# HOMADOS.net
KiCad netlist of a schematic drawn in EAGLE
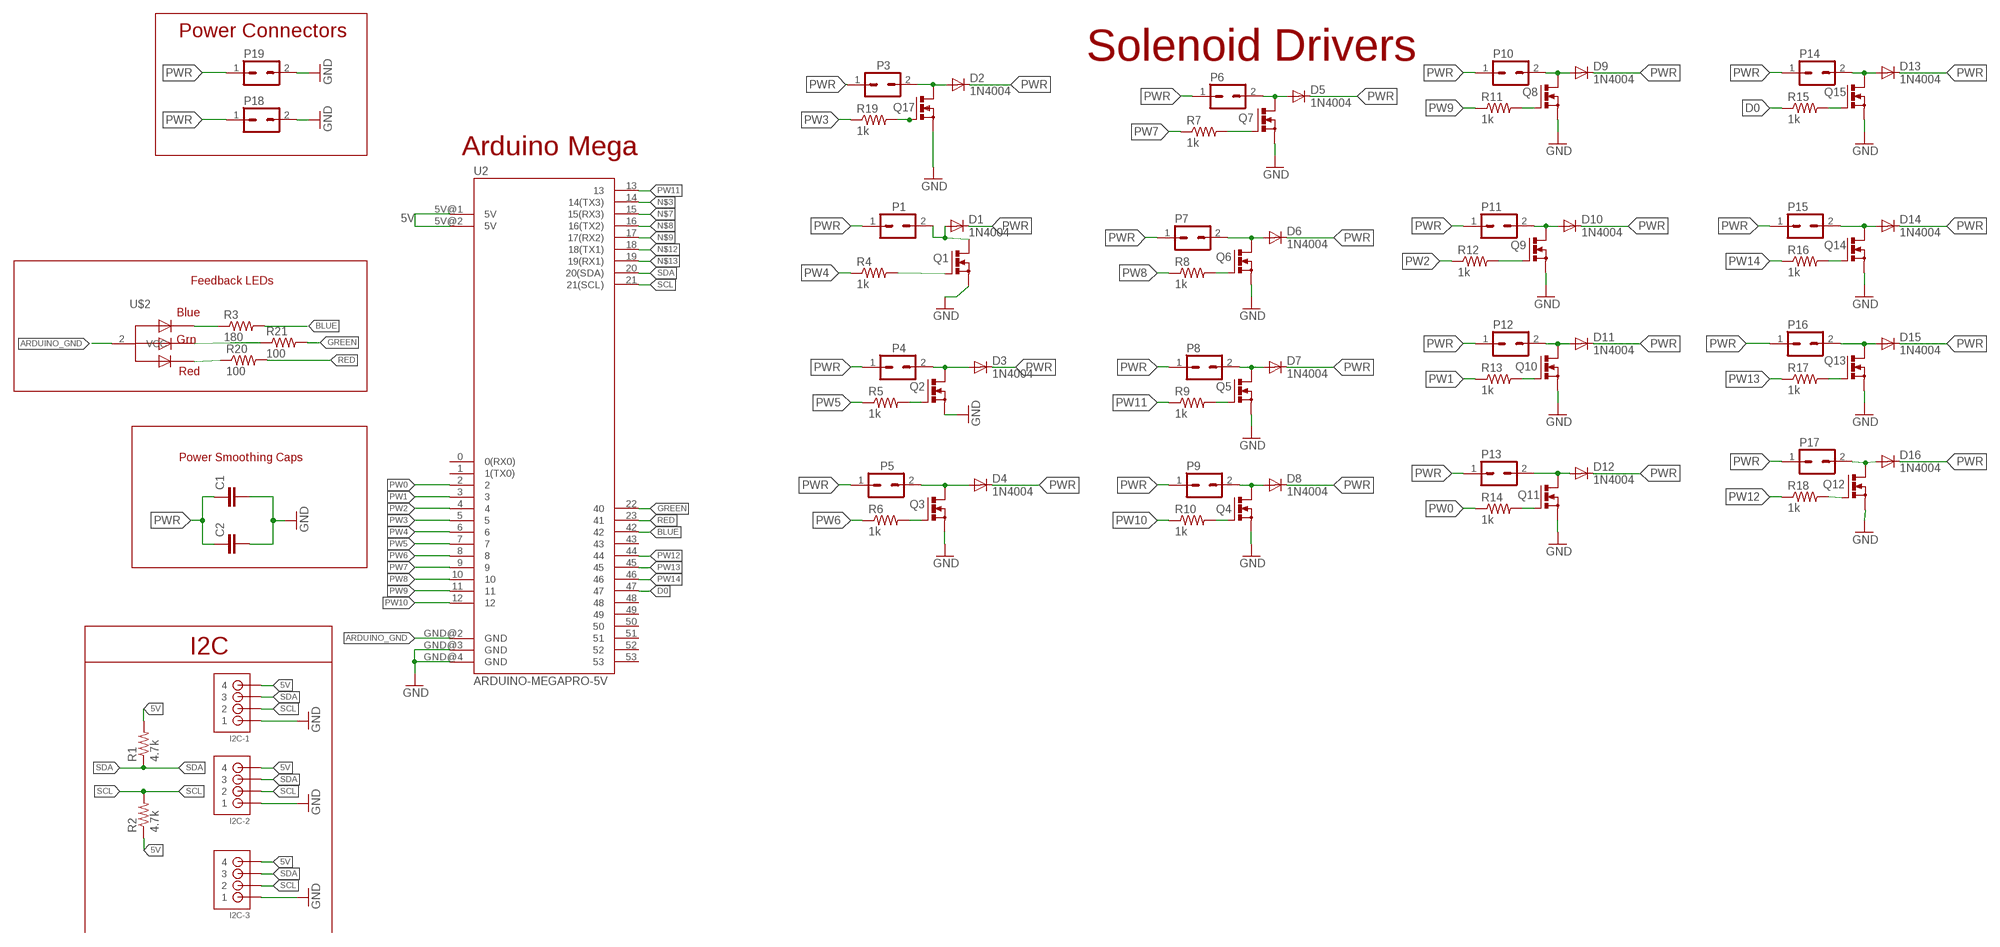
[diagram p0: schematic, sheet 1]

(export (version "E")
  (design (tool "Eeschema 10.0.6"))
  (components
    (comp (ref "C1")
      (value "CAPPTH1")
      (footprint "eagle-import:CAP-PTH-5MM")
      (libsource (lib "eagle-import") (part "CAPPTH1"))
    )
    (comp (ref "C2")
      (value "CAPPTH3")
      (footprint "eagle-import:CAP-PTH-LARGE")
      (libsource (lib "eagle-import") (part "CAPPTH3"))
    )
    (comp (ref "D1")
      (value "1N4004")
      (footprint "eagle-import:DO41-10")
      (libsource (lib "eagle-import") (part "1N4004"))
    )
    (comp (ref "D2")
      (value "1N4004")
      (footprint "eagle-import:DO41-10")
      (libsource (lib "eagle-import") (part "1N4004"))
    )
    (comp (ref "D3")
      (value "1N4004")
      (footprint "eagle-import:DO41-10")
      (libsource (lib "eagle-import") (part "1N4004"))
    )
    (comp (ref "D4")
      (value "1N4004")
      (footprint "eagle-import:DO41-10")
      (libsource (lib "eagle-import") (part "1N4004"))
    )
    (comp (ref "D5")
      (value "1N4004")
      (footprint "eagle-import:DO41-10")
      (libsource (lib "eagle-import") (part "1N4004"))
    )
    (comp (ref "D6")
      (value "1N4004")
      (footprint "eagle-import:DO41-10")
      (libsource (lib "eagle-import") (part "1N4004"))
    )
    (comp (ref "D7")
      (value "1N4004")
      (footprint "eagle-import:DO41-10")
      (libsource (lib "eagle-import") (part "1N4004"))
    )
    (comp (ref "D8")
      (value "1N4004")
      (footprint "eagle-import:DO41-10")
      (libsource (lib "eagle-import") (part "1N4004"))
    )
    (comp (ref "D9")
      (value "1N4004")
      (footprint "eagle-import:DO41-10")
      (libsource (lib "eagle-import") (part "1N4004"))
    )
    (comp (ref "D10")
      (value "1N4004")
      (footprint "eagle-import:DO41-10")
      (libsource (lib "eagle-import") (part "1N4004"))
    )
    (comp (ref "D11")
      (value "1N4004")
      (footprint "eagle-import:DO41-10")
      (libsource (lib "eagle-import") (part "1N4004"))
    )
    (comp (ref "D12")
      (value "1N4004")
      (footprint "eagle-import:DO41-10")
      (libsource (lib "eagle-import") (part "1N4004"))
    )
    (comp (ref "D13")
      (value "1N4004")
      (footprint "eagle-import:DO41-10")
      (libsource (lib "eagle-import") (part "1N4004"))
    )
    (comp (ref "D14")
      (value "1N4004")
      (footprint "eagle-import:DO41-10")
      (libsource (lib "eagle-import") (part "1N4004"))
    )
    (comp (ref "D15")
      (value "1N4004")
      (footprint "eagle-import:DO41-10")
      (libsource (lib "eagle-import") (part "1N4004"))
    )
    (comp (ref "D16")
      (value "1N4004")
      (footprint "eagle-import:DO41-10")
      (libsource (lib "eagle-import") (part "1N4004"))
    )
    (comp (ref "I2C-1")
      (value "JST-PH_4-PIN_HEADER")
      (footprint "eagle-import:JST_B4B-PH_HEADER")
      (libsource (lib "eagle-import") (part "JST-PH_4-PIN_HEADER"))
    )
    (comp (ref "I2C-2")
      (value "JST-PH_4-PIN_HEADER")
      (footprint "eagle-import:JST_B4B-PH_HEADER")
      (libsource (lib "eagle-import") (part "JST-PH_4-PIN_HEADER"))
    )
    (comp (ref "I2C-3")
      (value "JST-PH_4-PIN_HEADER")
      (footprint "eagle-import:JST_B4B-PH_HEADER")
      (libsource (lib "eagle-import") (part "JST-PH_4-PIN_HEADER"))
    )
    (comp (ref "P1")
      (value "39-30-02")
      (footprint "eagle-import:39-30-_02_")
      (libsource (lib "eagle-import") (part "39-30-?02?"))
    )
    (comp (ref "P3")
      (value "39-30-02")
      (footprint "eagle-import:39-30-_02_")
      (libsource (lib "eagle-import") (part "39-30-?02?"))
    )
    (comp (ref "P4")
      (value "39-30-02")
      (footprint "eagle-import:39-30-_02_")
      (libsource (lib "eagle-import") (part "39-30-?02?"))
    )
    (comp (ref "P5")
      (value "39-30-02")
      (footprint "eagle-import:39-30-_02_")
      (libsource (lib "eagle-import") (part "39-30-?02?"))
    )
    (comp (ref "P6")
      (value "39-30-02")
      (footprint "eagle-import:39-30-_02_")
      (libsource (lib "eagle-import") (part "39-30-?02?"))
    )
    (comp (ref "P7")
      (value "39-30-02")
      (footprint "eagle-import:39-30-_02_")
      (libsource (lib "eagle-import") (part "39-30-?02?"))
    )
    (comp (ref "P8")
      (value "39-30-02")
      (footprint "eagle-import:39-30-_02_")
      (libsource (lib "eagle-import") (part "39-30-?02?"))
    )
    (comp (ref "P9")
      (value "39-30-02")
      (footprint "eagle-import:39-30-_02_")
      (libsource (lib "eagle-import") (part "39-30-?02?"))
    )
    (comp (ref "P10")
      (value "39-30-02")
      (footprint "eagle-import:39-30-_02_")
      (libsource (lib "eagle-import") (part "39-30-?02?"))
    )
    (comp (ref "P11")
      (value "39-30-02")
      (footprint "eagle-import:39-30-_02_")
      (libsource (lib "eagle-import") (part "39-30-?02?"))
    )
    (comp (ref "P12")
      (value "39-30-02")
      (footprint "eagle-import:39-30-_02_")
      (libsource (lib "eagle-import") (part "39-30-?02?"))
    )
    (comp (ref "P13")
      (value "39-30-02")
      (footprint "eagle-import:39-30-_02_")
      (libsource (lib "eagle-import") (part "39-30-?02?"))
    )
    (comp (ref "P14")
      (value "39-30-02")
      (footprint "eagle-import:39-30-_02_")
      (libsource (lib "eagle-import") (part "39-30-?02?"))
    )
    (comp (ref "P15")
      (value "39-30-02")
      (footprint "eagle-import:39-30-_02_")
      (libsource (lib "eagle-import") (part "39-30-?02?"))
    )
    (comp (ref "P16")
      (value "39-30-02")
      (footprint "eagle-import:39-30-_02_")
      (libsource (lib "eagle-import") (part "39-30-?02?"))
    )
    (comp (ref "P17")
      (value "39-30-02")
      (footprint "eagle-import:39-30-_02_")
      (libsource (lib "eagle-import") (part "39-30-?02?"))
    )
    (comp (ref "P18")
      (value "39-30-02")
      (footprint "eagle-import:39-30-_02_")
      (libsource (lib "eagle-import") (part "39-30-?02?"))
    )
    (comp (ref "P19")
      (value "39-30-02")
      (footprint "eagle-import:39-30-_02_")
      (libsource (lib "eagle-import") (part "39-30-?02?"))
    )
    (comp (ref "Q1")
      (value "PMOSFET_NTO220BV")
      (footprint "eagle-import:TO220BV")
      (libsource (lib "eagle-import") (part "PMOSFET_NTO220BV"))
    )
    (comp (ref "Q2")
      (value "PMOSFET_NTO220BV")
      (footprint "eagle-import:TO220BV")
      (libsource (lib "eagle-import") (part "PMOSFET_NTO220BV"))
    )
    (comp (ref "Q3")
      (value "PMOSFET_NTO220BV")
      (footprint "eagle-import:TO220BV")
      (libsource (lib "eagle-import") (part "PMOSFET_NTO220BV"))
    )
    (comp (ref "Q4")
      (value "PMOSFET_NTO220BV")
      (footprint "eagle-import:TO220BV")
      (libsource (lib "eagle-import") (part "PMOSFET_NTO220BV"))
    )
    (comp (ref "Q5")
      (value "PMOSFET_NTO220BV")
      (footprint "eagle-import:TO220BV")
      (libsource (lib "eagle-import") (part "PMOSFET_NTO220BV"))
    )
    (comp (ref "Q6")
      (value "PMOSFET_NTO220BV")
      (footprint "eagle-import:TO220BV")
      (libsource (lib "eagle-import") (part "PMOSFET_NTO220BV"))
    )
    (comp (ref "Q7")
      (value "PMOSFET_NTO220BV")
      (footprint "eagle-import:TO220BV")
      (libsource (lib "eagle-import") (part "PMOSFET_NTO220BV"))
    )
    (comp (ref "Q8")
      (value "PMOSFET_NTO220BV")
      (footprint "eagle-import:TO220BV")
      (libsource (lib "eagle-import") (part "PMOSFET_NTO220BV"))
    )
    (comp (ref "Q9")
      (value "PMOSFET_NTO220BV")
      (footprint "eagle-import:TO220BV")
      (libsource (lib "eagle-import") (part "PMOSFET_NTO220BV"))
    )
    (comp (ref "Q10")
      (value "PMOSFET_NTO220BV")
      (footprint "eagle-import:TO220BV")
      (libsource (lib "eagle-import") (part "PMOSFET_NTO220BV"))
    )
    (comp (ref "Q11")
      (value "PMOSFET_NTO220BV")
      (footprint "eagle-import:TO220BV")
      (libsource (lib "eagle-import") (part "PMOSFET_NTO220BV"))
    )
    (comp (ref "Q12")
      (value "PMOSFET_NTO220BV")
      (footprint "eagle-import:TO220BV")
      (libsource (lib "eagle-import") (part "PMOSFET_NTO220BV"))
    )
    (comp (ref "Q13")
      (value "PMOSFET_NTO220BV")
      (footprint "eagle-import:TO220BV")
      (libsource (lib "eagle-import") (part "PMOSFET_NTO220BV"))
    )
    (comp (ref "Q14")
      (value "PMOSFET_NTO220BV")
      (footprint "eagle-import:TO220BV")
      (libsource (lib "eagle-import") (part "PMOSFET_NTO220BV"))
    )
    (comp (ref "Q15")
      (value "PMOSFET_NTO220BV")
      (footprint "eagle-import:TO220BV")
      (libsource (lib "eagle-import") (part "PMOSFET_NTO220BV"))
    )
    (comp (ref "Q17")
      (value "PMOSFET_NTO220BV")
      (footprint "eagle-import:TO220BV")
      (libsource (lib "eagle-import") (part "PMOSFET_NTO220BV"))
    )
    (comp (ref "R1")
      (value "4.7k")
      (footprint "eagle-import:AXIAL-0.3-KIT")
      (libsource (lib "eagle-import") (part "RESISTORKIT"))
    )
    (comp (ref "R2")
      (value "4.7k")
      (footprint "eagle-import:AXIAL-0.3-KIT")
      (libsource (lib "eagle-import") (part "RESISTORKIT"))
    )
    (comp (ref "R3")
      (value "180")
      (footprint "eagle-import:AXIAL-0.3-KIT")
      (libsource (lib "eagle-import") (part "RESISTORKIT"))
    )
    (comp (ref "R4")
      (value "1k")
      (footprint "eagle-import:AXIAL-0.3-KIT")
      (libsource (lib "eagle-import") (part "RESISTORKIT"))
    )
    (comp (ref "R5")
      (value "1k")
      (footprint "eagle-import:AXIAL-0.3-KIT")
      (libsource (lib "eagle-import") (part "RESISTORKIT"))
    )
    (comp (ref "R6")
      (value "1k")
      (footprint "eagle-import:AXIAL-0.3-KIT")
      (libsource (lib "eagle-import") (part "RESISTORKIT"))
    )
    (comp (ref "R7")
      (value "1k")
      (footprint "eagle-import:AXIAL-0.3-KIT")
      (libsource (lib "eagle-import") (part "RESISTORKIT"))
    )
    (comp (ref "R8")
      (value "1k")
      (footprint "eagle-import:AXIAL-0.3-KIT")
      (libsource (lib "eagle-import") (part "RESISTORKIT"))
    )
    (comp (ref "R9")
      (value "1k")
      (footprint "eagle-import:AXIAL-0.3-KIT")
      (libsource (lib "eagle-import") (part "RESISTORKIT"))
    )
    (comp (ref "R10")
      (value "1k")
      (footprint "eagle-import:AXIAL-0.3-KIT")
      (libsource (lib "eagle-import") (part "RESISTORKIT"))
    )
    (comp (ref "R11")
      (value "1k")
      (footprint "eagle-import:AXIAL-0.3-KIT")
      (libsource (lib "eagle-import") (part "RESISTORKIT"))
    )
    (comp (ref "R12")
      (value "1k")
      (footprint "eagle-import:AXIAL-0.3-KIT")
      (libsource (lib "eagle-import") (part "RESISTORKIT"))
    )
    (comp (ref "R13")
      (value "1k")
      (footprint "eagle-import:AXIAL-0.3-KIT")
      (libsource (lib "eagle-import") (part "RESISTORKIT"))
    )
    (comp (ref "R14")
      (value "1k")
      (footprint "eagle-import:AXIAL-0.3-KIT")
      (libsource (lib "eagle-import") (part "RESISTORKIT"))
    )
    (comp (ref "R15")
      (value "1k")
      (footprint "eagle-import:AXIAL-0.3-KIT")
      (libsource (lib "eagle-import") (part "RESISTORKIT"))
    )
    (comp (ref "R16")
      (value "1k")
      (footprint "eagle-import:AXIAL-0.3-KIT")
      (libsource (lib "eagle-import") (part "RESISTORKIT"))
    )
    (comp (ref "R17")
      (value "1k")
      (footprint "eagle-import:AXIAL-0.3-KIT")
      (libsource (lib "eagle-import") (part "RESISTORKIT"))
    )
    (comp (ref "R18")
      (value "1k")
      (footprint "eagle-import:AXIAL-0.3-KIT")
      (libsource (lib "eagle-import") (part "RESISTORKIT"))
    )
    (comp (ref "R19")
      (value "1k")
      (footprint "eagle-import:AXIAL-0.3-KIT")
      (libsource (lib "eagle-import") (part "RESISTORKIT"))
    )
    (comp (ref "R20")
      (value "100")
      (footprint "eagle-import:AXIAL-0.3-KIT")
      (libsource (lib "eagle-import") (part "RESISTORKIT"))
    )
    (comp (ref "R21")
      (value "100")
      (footprint "eagle-import:AXIAL-0.3-KIT")
      (libsource (lib "eagle-import") (part "RESISTORKIT"))
    )
    (comp (ref "U$2")
      (value "RGBLED_CA")
      (footprint "eagle-import:LED5MMRGB")
      (libsource (lib "eagle-import") (part "RGBLED_CA"))
    )
    (comp (ref "U2")
      (value "ARDUINO-MEGAPRO-5V")
      (footprint "eagle-import:ARDUINO_MEGA-PRO-5V")
      (libsource (lib "eagle-import") (part "ARDUINO-MEGAPRO-5V"))
    )
  )
  (nets
    (net (code "1") (name "5V") (class "Default")
      (node (ref "I2C-1") (pin "P4") (pinfunction "4_P4") (pintype "bidirectional"))
      (node (ref "I2C-2") (pin "P4") (pinfunction "4_P4") (pintype "bidirectional"))
      (node (ref "I2C-3") (pin "P4") (pinfunction "4_P4") (pintype "bidirectional"))
      (node (ref "R1") (pin "P$2") (pinfunction "2_P$2") (pintype "passive"))
      (node (ref "R2") (pin "P$1") (pinfunction "1_P$1") (pintype "passive"))
      (node (ref "U2") (pin "5V@1") (pinfunction "5V_5V@1") (pintype "bidirectional"))
      (node (ref "U2") (pin "5V@2") (pinfunction "5V_5V@2") (pintype "bidirectional"))
    )
    (net (code "2") (name "ARDUINO_GND") (class "Default")
      (node (ref "U$2") (pin "2") (pinfunction "VCC_2") (pintype "bidirectional"))
      (node (ref "U2") (pin "GND@2") (pinfunction "GND_GND@2") (pintype "bidirectional"))
    )
    (net (code "3") (name "BLUE") (class "Default")
      (node (ref "R3") (pin "P$2") (pinfunction "2_P$2") (pintype "passive"))
      (node (ref "U2") (pin "42") (pinfunction "42_42") (pintype "bidirectional"))
    )
    (net (code "4") (name "D0") (class "Default")
      (node (ref "R15") (pin "P$1") (pinfunction "1_P$1") (pintype "passive"))
      (node (ref "U2") (pin "47") (pinfunction "47_47") (pintype "bidirectional"))
    )
    (net (code "5") (name "GND") (class "Default")
      (node (ref "C1") (pin "2") (pinfunction "2_2") (pintype "passive"))
      (node (ref "C2") (pin "2") (pinfunction "2_2") (pintype "passive"))
      (node (ref "I2C-1") (pin "P1") (pinfunction "1_P1") (pintype "bidirectional"))
      (node (ref "I2C-2") (pin "P1") (pinfunction "1_P1") (pintype "bidirectional"))
      (node (ref "I2C-3") (pin "P1") (pinfunction "1_P1") (pintype "bidirectional"))
      (node (ref "P18") (pin "2") (pinfunction "2_2") (pintype "passive"))
      (node (ref "P19") (pin "2") (pinfunction "2_2") (pintype "passive"))
      (node (ref "Q1") (pin "S") (pinfunction "S_S") (pintype "passive"))
      (node (ref "Q10") (pin "S") (pinfunction "S_S") (pintype "passive"))
      (node (ref "Q11") (pin "S") (pinfunction "S_S") (pintype "passive"))
      (node (ref "Q12") (pin "S") (pinfunction "S_S") (pintype "passive"))
      (node (ref "Q13") (pin "S") (pinfunction "S_S") (pintype "passive"))
      (node (ref "Q14") (pin "S") (pinfunction "S_S") (pintype "passive"))
      (node (ref "Q15") (pin "S") (pinfunction "S_S") (pintype "passive"))
      (node (ref "Q17") (pin "S") (pinfunction "S_S") (pintype "passive"))
      (node (ref "Q2") (pin "S") (pinfunction "S_S") (pintype "passive"))
      (node (ref "Q3") (pin "S") (pinfunction "S_S") (pintype "passive"))
      (node (ref "Q4") (pin "S") (pinfunction "S_S") (pintype "passive"))
      (node (ref "Q5") (pin "S") (pinfunction "S_S") (pintype "passive"))
      (node (ref "Q6") (pin "S") (pinfunction "S_S") (pintype "passive"))
      (node (ref "Q7") (pin "S") (pinfunction "S_S") (pintype "passive"))
      (node (ref "Q8") (pin "S") (pinfunction "S_S") (pintype "passive"))
      (node (ref "Q9") (pin "S") (pinfunction "S_S") (pintype "passive"))
      (node (ref "U2") (pin "GND@3") (pinfunction "GND_GND@3") (pintype "bidirectional"))
      (node (ref "U2") (pin "GND@4") (pinfunction "GND_GND@4") (pintype "bidirectional"))
    )
    (net (code "6") (name "GREEN") (class "Default")
      (node (ref "R21") (pin "P$2") (pinfunction "2_P$2") (pintype "passive"))
      (node (ref "U2") (pin "22") (pinfunction "40_22") (pintype "bidirectional"))
    )
    (net (code "7") (name "N$3") (class "Default")
      (node (ref "U2") (pin "14") (pinfunction "14(TX3)_14") (pintype "bidirectional"))
    )
    (net (code "8") (name "N$7") (class "Default")
      (node (ref "U2") (pin "15") (pinfunction "15(RX3)_15") (pintype "bidirectional"))
    )
    (net (code "9") (name "N$8") (class "Default")
      (node (ref "U2") (pin "16") (pinfunction "16(TX2)_16") (pintype "bidirectional"))
    )
    (net (code "10") (name "N$9") (class "Default")
      (node (ref "U2") (pin "17") (pinfunction "17(RX2)_17") (pintype "bidirectional"))
    )
    (net (code "11") (name "N$12") (class "Default")
      (node (ref "U2") (pin "18") (pinfunction "18(TX1)_18") (pintype "bidirectional"))
    )
    (net (code "12") (name "N$13") (class "Default")
      (node (ref "U2") (pin "19") (pinfunction "19(RX1)_19") (pintype "bidirectional"))
    )
    (net (code "13") (name "Net-(D1-PadA)") (class "Default")
      (node (ref "D1") (pin "A") (pinfunction "A_A") (pintype "passive"))
      (node (ref "P1") (pin "2") (pinfunction "2_2") (pintype "passive"))
      (node (ref "Q1") (pin "D") (pinfunction "D_D") (pintype "passive"))
    )
    (net (code "14") (name "Net-(D2-PadA)") (class "Default")
      (node (ref "D2") (pin "A") (pinfunction "A_A") (pintype "passive"))
      (node (ref "P3") (pin "2") (pinfunction "2_2") (pintype "passive"))
      (node (ref "Q17") (pin "D") (pinfunction "D_D") (pintype "passive"))
    )
    (net (code "15") (name "Net-(D3-PadA)") (class "Default")
      (node (ref "D3") (pin "A") (pinfunction "A_A") (pintype "passive"))
      (node (ref "P4") (pin "2") (pinfunction "2_2") (pintype "passive"))
      (node (ref "Q2") (pin "D") (pinfunction "D_D") (pintype "passive"))
    )
    (net (code "16") (name "Net-(D4-PadA)") (class "Default")
      (node (ref "D4") (pin "A") (pinfunction "A_A") (pintype "passive"))
      (node (ref "P5") (pin "2") (pinfunction "2_2") (pintype "passive"))
      (node (ref "Q3") (pin "D") (pinfunction "D_D") (pintype "passive"))
    )
    (net (code "17") (name "Net-(D5-PadA)") (class "Default")
      (node (ref "D5") (pin "A") (pinfunction "A_A") (pintype "passive"))
      (node (ref "P6") (pin "2") (pinfunction "2_2") (pintype "passive"))
      (node (ref "Q7") (pin "D") (pinfunction "D_D") (pintype "passive"))
    )
    (net (code "18") (name "Net-(D6-PadA)") (class "Default")
      (node (ref "D6") (pin "A") (pinfunction "A_A") (pintype "passive"))
      (node (ref "P7") (pin "2") (pinfunction "2_2") (pintype "passive"))
      (node (ref "Q6") (pin "D") (pinfunction "D_D") (pintype "passive"))
    )
    (net (code "19") (name "Net-(D7-PadA)") (class "Default")
      (node (ref "D7") (pin "A") (pinfunction "A_A") (pintype "passive"))
      (node (ref "P8") (pin "2") (pinfunction "2_2") (pintype "passive"))
      (node (ref "Q5") (pin "D") (pinfunction "D_D") (pintype "passive"))
    )
    (net (code "20") (name "Net-(D8-PadA)") (class "Default")
      (node (ref "D8") (pin "A") (pinfunction "A_A") (pintype "passive"))
      (node (ref "P9") (pin "2") (pinfunction "2_2") (pintype "passive"))
      (node (ref "Q4") (pin "D") (pinfunction "D_D") (pintype "passive"))
    )
    (net (code "21") (name "Net-(D9-PadA)") (class "Default")
      (node (ref "D9") (pin "A") (pinfunction "A_A") (pintype "passive"))
      (node (ref "P10") (pin "2") (pinfunction "2_2") (pintype "passive"))
      (node (ref "Q8") (pin "D") (pinfunction "D_D") (pintype "passive"))
    )
    (net (code "22") (name "Net-(D10-PadA)") (class "Default")
      (node (ref "D10") (pin "A") (pinfunction "A_A") (pintype "passive"))
      (node (ref "P11") (pin "2") (pinfunction "2_2") (pintype "passive"))
      (node (ref "Q9") (pin "D") (pinfunction "D_D") (pintype "passive"))
    )
    (net (code "23") (name "Net-(D11-PadA)") (class "Default")
      (node (ref "D11") (pin "A") (pinfunction "A_A") (pintype "passive"))
      (node (ref "P12") (pin "2") (pinfunction "2_2") (pintype "passive"))
      (node (ref "Q10") (pin "D") (pinfunction "D_D") (pintype "passive"))
    )
    (net (code "24") (name "Net-(D12-PadA)") (class "Default")
      (node (ref "D12") (pin "A") (pinfunction "A_A") (pintype "passive"))
      (node (ref "P13") (pin "2") (pinfunction "2_2") (pintype "passive"))
      (node (ref "Q11") (pin "D") (pinfunction "D_D") (pintype "passive"))
    )
    (net (code "25") (name "Net-(D13-PadA)") (class "Default")
      (node (ref "D13") (pin "A") (pinfunction "A_A") (pintype "passive"))
      (node (ref "P14") (pin "2") (pinfunction "2_2") (pintype "passive"))
      (node (ref "Q15") (pin "D") (pinfunction "D_D") (pintype "passive"))
    )
    (net (code "26") (name "Net-(D14-PadA)") (class "Default")
      (node (ref "D14") (pin "A") (pinfunction "A_A") (pintype "passive"))
      (node (ref "P15") (pin "2") (pinfunction "2_2") (pintype "passive"))
      (node (ref "Q14") (pin "D") (pinfunction "D_D") (pintype "passive"))
    )
    (net (code "27") (name "Net-(D15-PadA)") (class "Default")
      (node (ref "D15") (pin "A") (pinfunction "A_A") (pintype "passive"))
      (node (ref "P16") (pin "2") (pinfunction "2_2") (pintype "passive"))
      (node (ref "Q13") (pin "D") (pinfunction "D_D") (pintype "passive"))
    )
    (net (code "28") (name "Net-(D16-PadA)") (class "Default")
      (node (ref "D16") (pin "A") (pinfunction "A_A") (pintype "passive"))
      (node (ref "P17") (pin "2") (pinfunction "2_2") (pintype "passive"))
      (node (ref "Q12") (pin "D") (pinfunction "D_D") (pintype "passive"))
    )
    (net (code "29") (name "Net-(R3-1)") (class "Default")
      (node (ref "R3") (pin "P$1") (pinfunction "1_P$1") (pintype "passive"))
      (node (ref "U$2") (pin "4") (pinfunction "BLUE_4") (pintype "bidirectional"))
    )
    (net (code "30") (name "Net-(R4-2)") (class "Default")
      (node (ref "Q1") (pin "G") (pinfunction "G_G") (pintype "passive"))
      (node (ref "R4") (pin "P$2") (pinfunction "2_P$2") (pintype "passive"))
    )
    (net (code "31") (name "Net-(R5-2)") (class "Default")
      (node (ref "Q2") (pin "G") (pinfunction "G_G") (pintype "passive"))
      (node (ref "R5") (pin "P$2") (pinfunction "2_P$2") (pintype "passive"))
    )
    (net (code "32") (name "Net-(R6-2)") (class "Default")
      (node (ref "Q3") (pin "G") (pinfunction "G_G") (pintype "passive"))
      (node (ref "R6") (pin "P$2") (pinfunction "2_P$2") (pintype "passive"))
    )
    (net (code "33") (name "Net-(R7-2)") (class "Default")
      (node (ref "Q7") (pin "G") (pinfunction "G_G") (pintype "passive"))
      (node (ref "R7") (pin "P$2") (pinfunction "2_P$2") (pintype "passive"))
    )
    (net (code "34") (name "Net-(R8-2)") (class "Default")
      (node (ref "Q6") (pin "G") (pinfunction "G_G") (pintype "passive"))
      (node (ref "R8") (pin "P$2") (pinfunction "2_P$2") (pintype "passive"))
    )
    (net (code "35") (name "Net-(R9-2)") (class "Default")
      (node (ref "Q5") (pin "G") (pinfunction "G_G") (pintype "passive"))
      (node (ref "R9") (pin "P$2") (pinfunction "2_P$2") (pintype "passive"))
    )
    (net (code "36") (name "Net-(R10-2)") (class "Default")
      (node (ref "Q4") (pin "G") (pinfunction "G_G") (pintype "passive"))
      (node (ref "R10") (pin "P$2") (pinfunction "2_P$2") (pintype "passive"))
    )
    (net (code "37") (name "Net-(R11-2)") (class "Default")
      (node (ref "Q8") (pin "G") (pinfunction "G_G") (pintype "passive"))
      (node (ref "R11") (pin "P$2") (pinfunction "2_P$2") (pintype "passive"))
    )
    (net (code "38") (name "Net-(R12-2)") (class "Default")
      (node (ref "Q9") (pin "G") (pinfunction "G_G") (pintype "passive"))
      (node (ref "R12") (pin "P$2") (pinfunction "2_P$2") (pintype "passive"))
    )
    (net (code "39") (name "Net-(R13-2)") (class "Default")
      (node (ref "Q10") (pin "G") (pinfunction "G_G") (pintype "passive"))
      (node (ref "R13") (pin "P$2") (pinfunction "2_P$2") (pintype "passive"))
    )
    (net (code "40") (name "Net-(R14-2)") (class "Default")
      (node (ref "Q11") (pin "G") (pinfunction "G_G") (pintype "passive"))
      (node (ref "R14") (pin "P$2") (pinfunction "2_P$2") (pintype "passive"))
    )
    (net (code "41") (name "Net-(R15-2)") (class "Default")
      (node (ref "Q15") (pin "G") (pinfunction "G_G") (pintype "passive"))
      (node (ref "R15") (pin "P$2") (pinfunction "2_P$2") (pintype "passive"))
    )
    (net (code "42") (name "Net-(R16-2)") (class "Default")
      (node (ref "Q14") (pin "G") (pinfunction "G_G") (pintype "passive"))
      (node (ref "R16") (pin "P$2") (pinfunction "2_P$2") (pintype "passive"))
    )
    (net (code "43") (name "Net-(R17-2)") (class "Default")
      (node (ref "Q13") (pin "G") (pinfunction "G_G") (pintype "passive"))
      (node (ref "R17") (pin "P$2") (pinfunction "2_P$2") (pintype "passive"))
    )
    (net (code "44") (name "Net-(R18-2)") (class "Default")
      (node (ref "Q12") (pin "G") (pinfunction "G_G") (pintype "passive"))
      (node (ref "R18") (pin "P$2") (pinfunction "2_P$2") (pintype "passive"))
    )
    (net (code "45") (name "Net-(R19-2)") (class "Default")
      (node (ref "Q17") (pin "G") (pinfunction "G_G") (pintype "passive"))
      (node (ref "R19") (pin "P$2") (pinfunction "2_P$2") (pintype "passive"))
    )
    (net (code "46") (name "Net-(R20-1)") (class "Default")
      (node (ref "R20") (pin "P$1") (pinfunction "1_P$1") (pintype "passive"))
      (node (ref "U$2") (pin "1") (pinfunction "RED_1") (pintype "bidirectional"))
    )
    (net (code "47") (name "Net-(R21-1)") (class "Default")
      (node (ref "R21") (pin "P$1") (pinfunction "1_P$1") (pintype "passive"))
      (node (ref "U$2") (pin "3") (pinfunction "GREEN_3") (pintype "bidirectional"))
    )
    (net (code "48") (name "PW0") (class "Default")
      (node (ref "R14") (pin "P$1") (pinfunction "1_P$1") (pintype "passive"))
      (node (ref "U2") (pin "2") (pinfunction "2_2") (pintype "bidirectional"))
    )
    (net (code "49") (name "PW1") (class "Default")
      (node (ref "R13") (pin "P$1") (pinfunction "1_P$1") (pintype "passive"))
      (node (ref "U2") (pin "3") (pinfunction "3_3") (pintype "bidirectional"))
    )
    (net (code "50") (name "PW2") (class "Default")
      (node (ref "R12") (pin "P$1") (pinfunction "1_P$1") (pintype "passive"))
      (node (ref "U2") (pin "4") (pinfunction "4_4") (pintype "bidirectional"))
    )
    (net (code "51") (name "PW3") (class "Default")
      (node (ref "R19") (pin "P$1") (pinfunction "1_P$1") (pintype "passive"))
      (node (ref "U2") (pin "5") (pinfunction "5_5") (pintype "bidirectional"))
    )
    (net (code "52") (name "PW4") (class "Default")
      (node (ref "R4") (pin "P$1") (pinfunction "1_P$1") (pintype "passive"))
      (node (ref "U2") (pin "6") (pinfunction "6_6") (pintype "bidirectional"))
    )
    (net (code "53") (name "PW5") (class "Default")
      (node (ref "R5") (pin "P$1") (pinfunction "1_P$1") (pintype "passive"))
      (node (ref "U2") (pin "7") (pinfunction "7_7") (pintype "bidirectional"))
    )
    (net (code "54") (name "PW6") (class "Default")
      (node (ref "R6") (pin "P$1") (pinfunction "1_P$1") (pintype "passive"))
      (node (ref "U2") (pin "8") (pinfunction "8_8") (pintype "bidirectional"))
    )
    (net (code "55") (name "PW7") (class "Default")
      (node (ref "R7") (pin "P$1") (pinfunction "1_P$1") (pintype "passive"))
      (node (ref "U2") (pin "9") (pinfunction "9_9") (pintype "bidirectional"))
    )
    (net (code "56") (name "PW8") (class "Default")
      (node (ref "R8") (pin "P$1") (pinfunction "1_P$1") (pintype "passive"))
      (node (ref "U2") (pin "10") (pinfunction "10_10") (pintype "bidirectional"))
    )
    (net (code "57") (name "PW9") (class "Default")
      (node (ref "R11") (pin "P$1") (pinfunction "1_P$1") (pintype "passive"))
      (node (ref "U2") (pin "11") (pinfunction "11_11") (pintype "bidirectional"))
    )
    (net (code "58") (name "PW10") (class "Default")
      (node (ref "R10") (pin "P$1") (pinfunction "1_P$1") (pintype "passive"))
      (node (ref "U2") (pin "12") (pinfunction "12_12") (pintype "bidirectional"))
    )
    (net (code "59") (name "PW11") (class "Default")
      (node (ref "R9") (pin "P$1") (pinfunction "1_P$1") (pintype "passive"))
      (node (ref "U2") (pin "13") (pinfunction "13_13") (pintype "bidirectional"))
    )
    (net (code "60") (name "PW12") (class "Default")
      (node (ref "R18") (pin "P$1") (pinfunction "1_P$1") (pintype "passive"))
      (node (ref "U2") (pin "44") (pinfunction "44_44") (pintype "bidirectional"))
    )
    (net (code "61") (name "PW13") (class "Default")
      (node (ref "R17") (pin "P$1") (pinfunction "1_P$1") (pintype "passive"))
      (node (ref "U2") (pin "45") (pinfunction "45_45") (pintype "bidirectional"))
    )
    (net (code "62") (name "PW14") (class "Default")
      (node (ref "R16") (pin "P$1") (pinfunction "1_P$1") (pintype "passive"))
      (node (ref "U2") (pin "46") (pinfunction "46_46") (pintype "bidirectional"))
    )
    (net (code "63") (name "PWR") (class "Default")
      (node (ref "C1") (pin "1") (pinfunction "1_1") (pintype "passive"))
      (node (ref "C2") (pin "1") (pinfunction "1_1") (pintype "passive"))
      (node (ref "D1") (pin "C") (pinfunction "C_C") (pintype "passive"))
      (node (ref "D10") (pin "C") (pinfunction "C_C") (pintype "passive"))
      (node (ref "D11") (pin "C") (pinfunction "C_C") (pintype "passive"))
      (node (ref "D12") (pin "C") (pinfunction "C_C") (pintype "passive"))
      (node (ref "D13") (pin "C") (pinfunction "C_C") (pintype "passive"))
      (node (ref "D14") (pin "C") (pinfunction "C_C") (pintype "passive"))
      (node (ref "D15") (pin "C") (pinfunction "C_C") (pintype "passive"))
      (node (ref "D16") (pin "C") (pinfunction "C_C") (pintype "passive"))
      (node (ref "D2") (pin "C") (pinfunction "C_C") (pintype "passive"))
      (node (ref "D3") (pin "C") (pinfunction "C_C") (pintype "passive"))
      (node (ref "D4") (pin "C") (pinfunction "C_C") (pintype "passive"))
      (node (ref "D5") (pin "C") (pinfunction "C_C") (pintype "passive"))
      (node (ref "D6") (pin "C") (pinfunction "C_C") (pintype "passive"))
      (node (ref "D7") (pin "C") (pinfunction "C_C") (pintype "passive"))
      (node (ref "D8") (pin "C") (pinfunction "C_C") (pintype "passive"))
      (node (ref "D9") (pin "C") (pinfunction "C_C") (pintype "passive"))
      (node (ref "P1") (pin "1") (pinfunction "1_1") (pintype "passive"))
      (node (ref "P10") (pin "1") (pinfunction "1_1") (pintype "passive"))
      (node (ref "P11") (pin "1") (pinfunction "1_1") (pintype "passive"))
      (node (ref "P12") (pin "1") (pinfunction "1_1") (pintype "passive"))
      (node (ref "P13") (pin "1") (pinfunction "1_1") (pintype "passive"))
      (node (ref "P14") (pin "1") (pinfunction "1_1") (pintype "passive"))
      (node (ref "P15") (pin "1") (pinfunction "1_1") (pintype "passive"))
      (node (ref "P16") (pin "1") (pinfunction "1_1") (pintype "passive"))
      (node (ref "P17") (pin "1") (pinfunction "1_1") (pintype "passive"))
      (node (ref "P18") (pin "1") (pinfunction "1_1") (pintype "passive"))
      (node (ref "P19") (pin "1") (pinfunction "1_1") (pintype "passive"))
      (node (ref "P3") (pin "1") (pinfunction "1_1") (pintype "passive"))
      (node (ref "P4") (pin "1") (pinfunction "1_1") (pintype "passive"))
      (node (ref "P5") (pin "1") (pinfunction "1_1") (pintype "passive"))
      (node (ref "P6") (pin "1") (pinfunction "1_1") (pintype "passive"))
      (node (ref "P7") (pin "1") (pinfunction "1_1") (pintype "passive"))
      (node (ref "P8") (pin "1") (pinfunction "1_1") (pintype "passive"))
      (node (ref "P9") (pin "1") (pinfunction "1_1") (pintype "passive"))
    )
    (net (code "64") (name "RED") (class "Default")
      (node (ref "R20") (pin "P$2") (pinfunction "2_P$2") (pintype "passive"))
      (node (ref "U2") (pin "23") (pinfunction "41_23") (pintype "bidirectional"))
    )
    (net (code "65") (name "SCL") (class "Default")
      (node (ref "I2C-1") (pin "P2") (pinfunction "2_P2") (pintype "bidirectional"))
      (node (ref "I2C-2") (pin "P2") (pinfunction "2_P2") (pintype "bidirectional"))
      (node (ref "I2C-3") (pin "P2") (pinfunction "2_P2") (pintype "bidirectional"))
      (node (ref "R2") (pin "P$2") (pinfunction "2_P$2") (pintype "passive"))
      (node (ref "U2") (pin "21") (pinfunction "21(SCL)_21") (pintype "bidirectional"))
    )
    (net (code "66") (name "SDA") (class "Default")
      (node (ref "I2C-1") (pin "P3") (pinfunction "3_P3") (pintype "bidirectional"))
      (node (ref "I2C-2") (pin "P3") (pinfunction "3_P3") (pintype "bidirectional"))
      (node (ref "I2C-3") (pin "P3") (pinfunction "3_P3") (pintype "bidirectional"))
      (node (ref "R1") (pin "P$1") (pinfunction "1_P$1") (pintype "passive"))
      (node (ref "U2") (pin "20") (pinfunction "20(SDA)_20") (pintype "bidirectional"))
    )
    (net (code "67") (name "unconnected-(U2-0(RX0)-Pad0)") (class "Default")
      (node (ref "U2") (pin "0") (pinfunction "0(RX0)_0") (pintype "bidirectional"))
    )
    (net (code "68") (name "unconnected-(U2-1(TX0)-Pad1)") (class "Default")
      (node (ref "U2") (pin "1") (pinfunction "1(TX0)_1") (pintype "bidirectional"))
    )
    (net (code "69") (name "unconnected-(U2-Pad43)") (class "Default")
      (node (ref "U2") (pin "43") (pinfunction "43_43") (pintype "bidirectional"))
    )
    (net (code "70") (name "unconnected-(U2-Pad48)") (class "Default")
      (node (ref "U2") (pin "48") (pinfunction "48_48") (pintype "bidirectional"))
    )
    (net (code "71") (name "unconnected-(U2-Pad49)") (class "Default")
      (node (ref "U2") (pin "49") (pinfunction "49_49") (pintype "bidirectional"))
    )
    (net (code "72") (name "unconnected-(U2-Pad50)") (class "Default")
      (node (ref "U2") (pin "50") (pinfunction "50_50") (pintype "bidirectional"))
    )
    (net (code "73") (name "unconnected-(U2-Pad51)") (class "Default")
      (node (ref "U2") (pin "51") (pinfunction "51_51") (pintype "bidirectional"))
    )
    (net (code "74") (name "unconnected-(U2-Pad52)") (class "Default")
      (node (ref "U2") (pin "52") (pinfunction "52_52") (pintype "bidirectional"))
    )
    (net (code "75") (name "unconnected-(U2-Pad53)") (class "Default")
      (node (ref "U2") (pin "53") (pinfunction "53_53") (pintype "bidirectional"))
    )
  )
)
